# Master_Board_v1_110116.net
KiCad netlist of a schematic drawn in Altium Designer
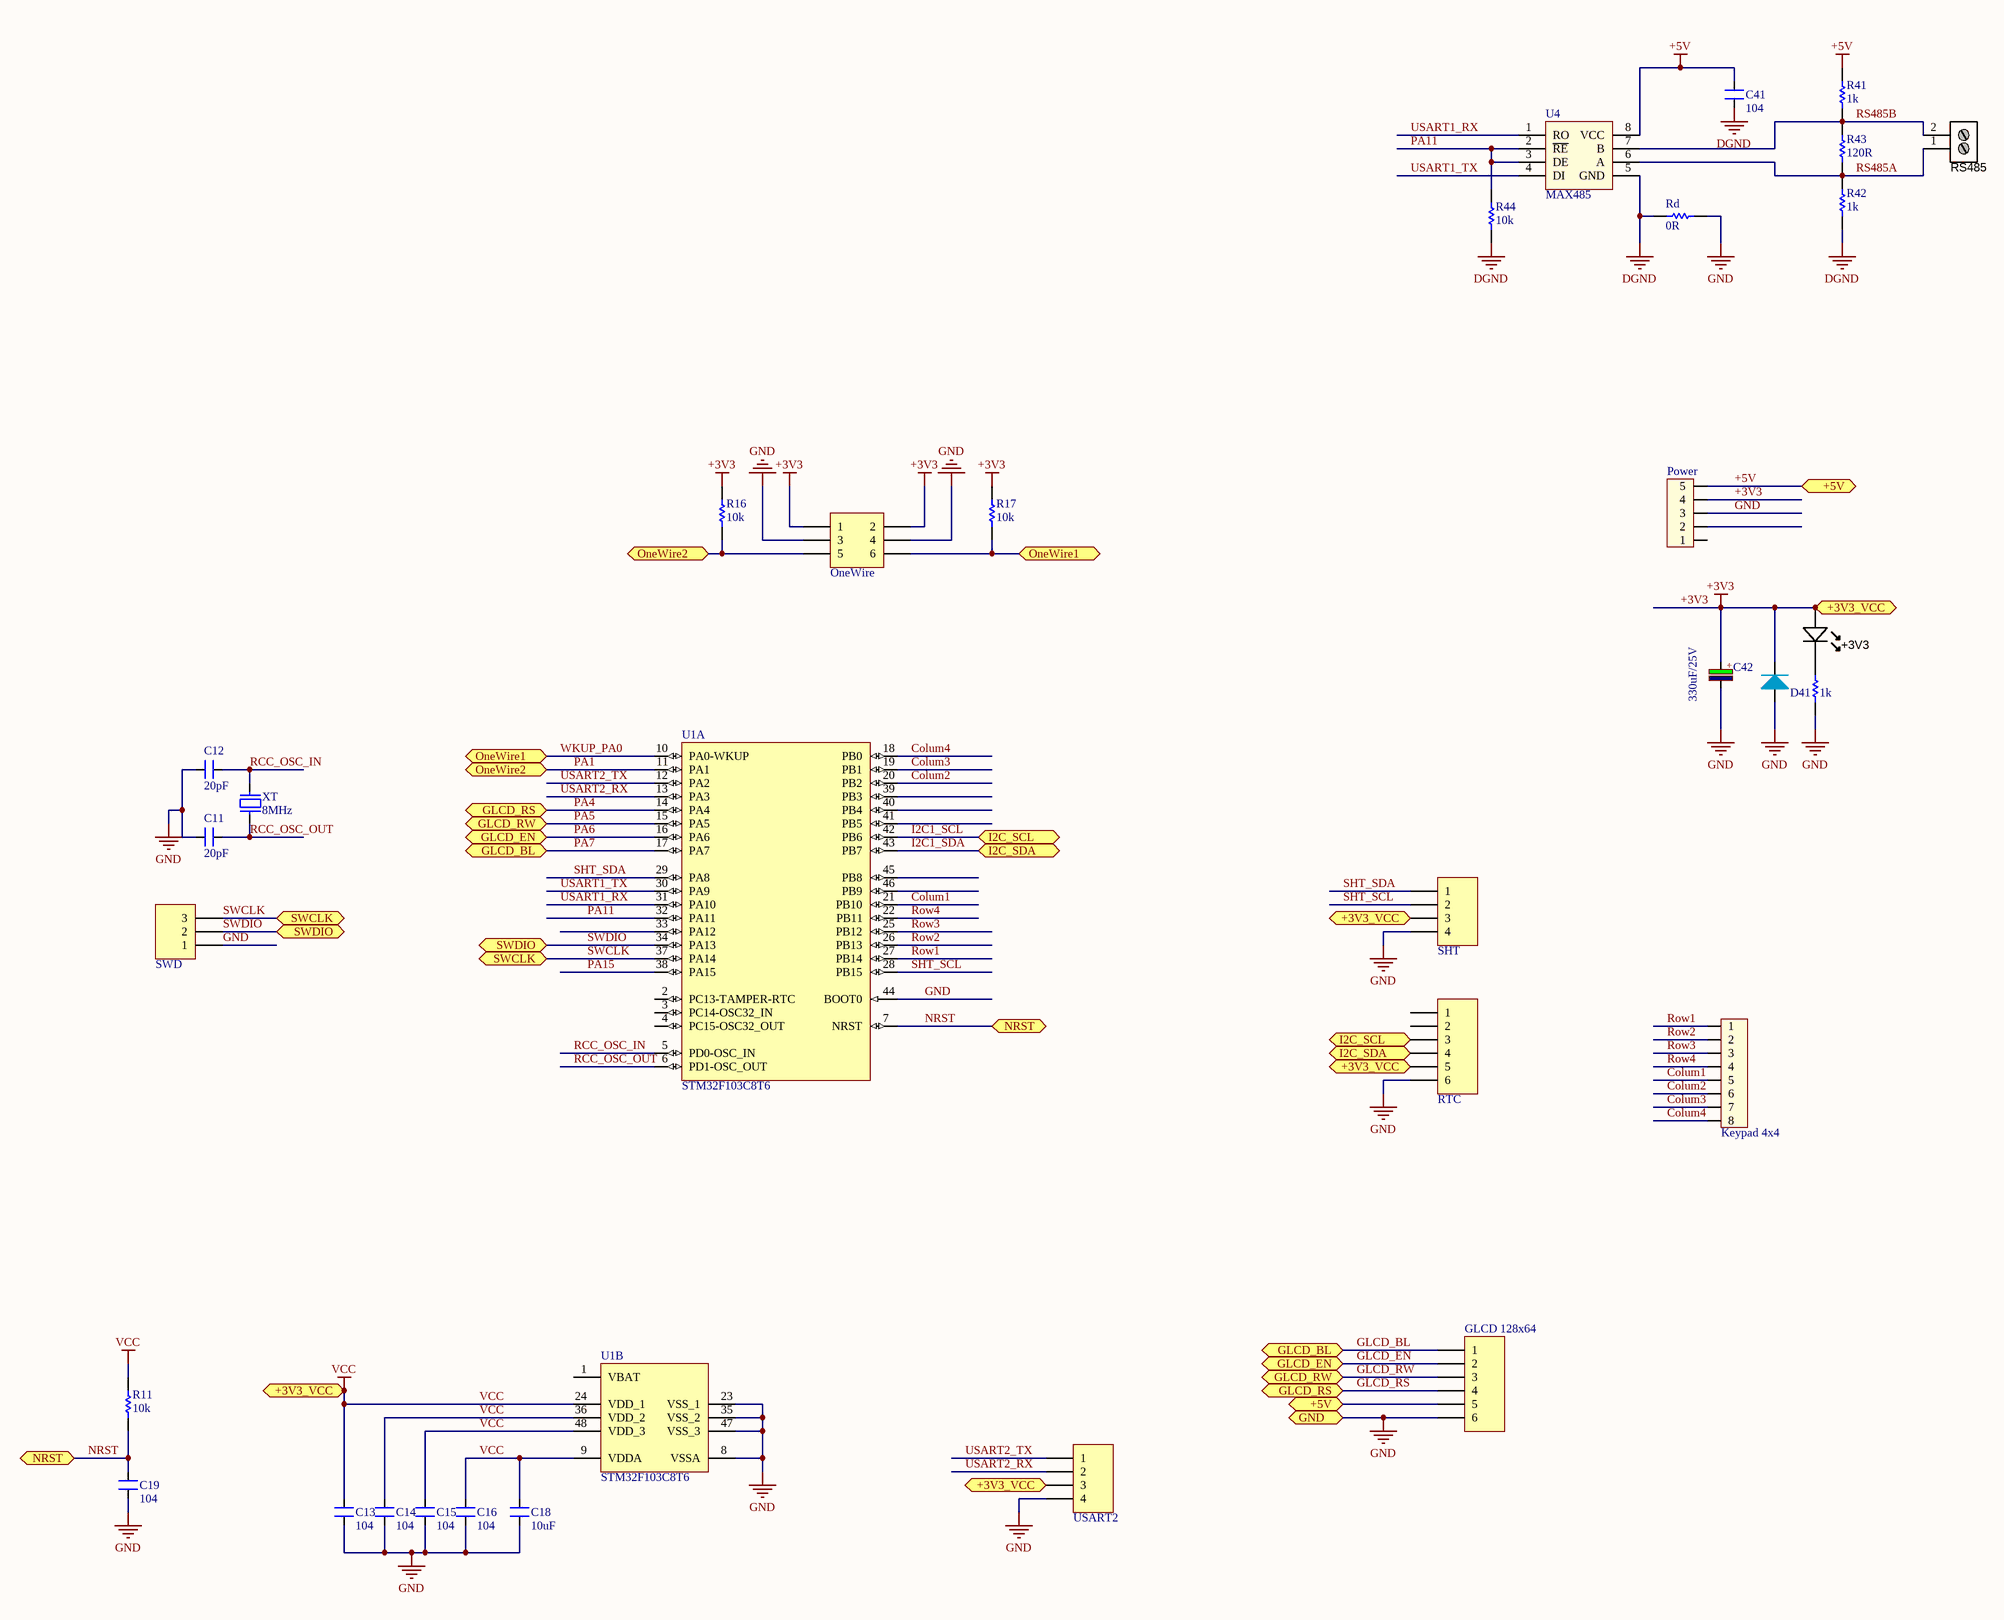
[diagram p0: Master_Board_v1_110116.SchDoc]

(export (version "E")
  (design (tool "Eeschema 10.0.6"))
  (components
    (comp (ref "+3V3")
      (value "Blue")
      (footprint "LED-0805-K")
      (description "LED 0805 SMD Blue 100mcd 470nm")
      (libsource (lib "PBL - Light Sources") (part "LED_SMD_Blue_0805_100mcd"))
    )
    (comp (ref "C11")
      (value "20pF")
      (footprint "CAPC1608N")
      (fields (field (name "Comment") "Cap_22p_0603"))
      (libsource (lib "Tuan") (part "CAP NP"))
    )
    (comp (ref "C12")
      (value "20pF")
      (footprint "CAPC1608N")
      (fields (field (name "Comment") "Cap_22p_0603"))
      (libsource (lib "Tuan") (part "CAP NP"))
    )
    (comp (ref "C13")
      (value "104")
      (footprint "CAPC1608N")
      (fields (field (name "Comment") "Cap_104_0603"))
      (libsource (lib "Tuan") (part "CAP NP"))
    )
    (comp (ref "C14")
      (value "104")
      (footprint "CAPC1608N")
      (fields (field (name "Comment") "Cap_104_0603"))
      (libsource (lib "Tuan") (part "CAP NP"))
    )
    (comp (ref "C15")
      (value "104")
      (footprint "CAPC1608N")
      (fields (field (name "Comment") "Cap_104_0603"))
      (libsource (lib "Tuan") (part "CAP NP"))
    )
    (comp (ref "C16")
      (value "104")
      (footprint "CAPC1608N")
      (fields (field (name "Comment") "Cap_104_0603"))
      (libsource (lib "Tuan") (part "CAP NP"))
    )
    (comp (ref "C18")
      (value "10uF")
      (footprint "CAPC2012N_F")
      (fields (field (name "Comment") "Cap_10uF_0805"))
      (libsource (lib "Tuan") (part "CAP NP"))
    )
    (comp (ref "C19")
      (value "104")
      (footprint "CAPC1608N")
      (fields (field (name "Comment") "Cap_104_0603"))
      (libsource (lib "Tuan") (part "CAP NP"))
    )
    (comp (ref "C41")
      (value "104")
      (footprint "CAPC2012N_F")
      (fields (field (name "Comment") "100nF/104"))
      (libsource (lib "Tuan") (part "CAP NP"))
    )
    (comp (ref "C42")
      (value "330uF/25V")
      (footprint "CAPMP3528X210N")
      (description "Cap 1000uF/16V - 220uF/50V")
      (libsource (lib "heromap") (part "CP4"))
    )
    (comp (ref "D41") (value "Diode") (footprint "DO-214AC") (libsource (lib "Tuan") (part "Diode")))
    (comp (ref "GLCD 128x64")
      (value "Header 6")
      (footprint "HDR1X6")
      (description "Header, 6-Pin")
      (fields (field (name "PUBLISHER") "Altium Limited"))
      (libsource (lib "Miscellaneous Connectors") (part "Header 6"))
    )
    (comp (ref "Keypad 4x4")
      (value "JP8")
      (footprint "CON8")
      (description "Connector 8")
      (libsource (lib "syhaunguyen") (part "Con8"))
    )
    (comp (ref "OneWire")
      (value "Header 3X2")
      (footprint "heromap:HDR2X3")
      (description "Header, 3-Pin, Dual row")
      (fields (field (name "PUBLISHER") "Altium Limited"))
      (libsource (lib "heromap") (part "Header 3X2"))
    )
    (comp (ref "Power")
      (value "JP5")
      (footprint "heromap:CON5")
      (description "Connector 5")
      (libsource (lib "heromap") (part "Con5"))
    )
    (comp (ref "R11")
      (value "10k")
      (footprint "RESC1608N_F")
      (fields (field (name "Comment") "Res_10k_0603"))
      (libsource (lib "Tuan") (part "Res"))
    )
    (comp (ref "R16")
      (value "10k")
      (footprint "RESC2012N_F")
      (fields (field (name "Comment") "Res"))
      (libsource (lib "Tuan") (part "Res"))
    )
    (comp (ref "R17")
      (value "10k")
      (footprint "RESC2012N_F")
      (fields (field (name "Comment") "Res"))
      (libsource (lib "Tuan") (part "Res"))
    )
    (comp (ref "R41")
      (value "1k")
      (footprint "RESC2012N_F")
      (description "Tro dan")
      (libsource (lib "GPS_Clock_v12") (part "Res"))
    )
    (comp (ref "R42")
      (value "1k")
      (footprint "RESC2012N_F")
      (description "Tro dan")
      (libsource (lib "GPS_Clock_v12") (part "Res"))
    )
    (comp (ref "R43")
      (value "120R")
      (footprint "RESC2012N_F")
      (description "Tro dan")
      (fields (field (name "Comment") "330R"))
      (libsource (lib "GPS_Clock_v12") (part "Res"))
    )
    (comp (ref "R44")
      (value "10k")
      (footprint "RESC2012N_F")
      (description "Tro dan")
      (fields (field (name "Comment") "330R"))
      (libsource (lib "GPS_Clock_v12") (part "Res"))
    )
    (comp (ref "Rd")
      (value "0R")
      (footprint "RESC2012N_F")
      (fields (field (name "Comment") "Res"))
      (libsource (lib "Tuan") (part "Res"))
    )
    (comp (ref "Rled")
      (value "1k")
      (footprint "RESC2012N_F")
      (fields (field (name "Comment") "Res_0805_1k"))
      (libsource (lib "Tuan") (part "Res"))
    )
    (comp (ref "RS485")
      (value "Stackable ScrewTerm")
      (footprint "2P_PCB1")
      (description "Terminal Block Screw Type THT 2-Position 3.81mm pitch")
      (libsource (lib "PBL - Connectors") (part "2P_ScrewTerm_90S_3.81MM"))
    )
    (comp (ref "RTC")
      (value "Header 6")
      (footprint "heromap:HDR1X6")
      (description "Header, 6-Pin")
      (fields (field (name "PUBLISHER") "Altium Limited"))
      (libsource (lib "heromap") (part "Header 6"))
    )
    (comp (ref "SHT")
      (value "Header 4")
      (footprint "heromap:HDR1X4")
      (description "Header, 4-Pin")
      (fields (field (name "PUBLISHER") "Altium Limited"))
      (libsource (lib "heromap") (part "Header 4"))
    )
    (comp (ref "SWD")
      (value "Header 3")
      (footprint "heromap:HDR1X3")
      (description "Header, 3-Pin")
      (fields (field (name "PUBLISHER") "Altium Limited"))
      (libsource (lib "heromap") (part "Header 3"))
    )
    (comp (ref "U1")
      (value "STM32F103C8T6")
      (footprint "LQFT48N")
      (libsource (lib "STMicroelectronics STM32 F1") (part "STM32F103C8T6"))
    )
    (comp (ref "U4")
      (value "MAX485")
      (footprint "SO-8")
      (description "RS232 - RS485 (Same sn75176)")
      (libsource (lib "heromap") (part "MAX485"))
    )
    (comp (ref "USART2")
      (value "Header 4")
      (footprint "heromap:HDR1X4")
      (description "Header, 4-Pin")
      (fields (field (name "PUBLISHER") "Altium Limited"))
      (libsource (lib "heromap") (part "Header 4"))
    )
    (comp (ref "XT") (value "8MHz") (footprint "XT2") (libsource (lib "Tuan") (part "Crystal")))
  )
  (nets
    (net (code "1") (name "+3V3") (class "Default")
      (node (ref "+3V3") (pin "A") (pinfunction "A_A") (pintype "passive"))
      (node (ref "C13") (pin "2") (pinfunction "2_2") (pintype "passive"))
      (node (ref "C14") (pin "2") (pinfunction "2_2") (pintype "passive"))
      (node (ref "C15") (pin "2") (pinfunction "2_2") (pintype "passive"))
      (node (ref "C16") (pin "2") (pinfunction "2_2") (pintype "passive"))
      (node (ref "C18") (pin "2") (pinfunction "2_2") (pintype "passive"))
      (node (ref "C42") (pin "1") (pinfunction "1_1") (pintype "passive"))
      (node (ref "D41") (pin "2") (pinfunction "K_2") (pintype "passive"))
      (node (ref "OneWire") (pin "1") (pinfunction "1_1") (pintype "passive"))
      (node (ref "OneWire") (pin "2") (pinfunction "2_2") (pintype "passive"))
      (node (ref "Power") (pin "4") (pinfunction "4_4") (pintype "passive"))
      (node (ref "R11") (pin "2") (pinfunction "2_2") (pintype "passive"))
      (node (ref "R16") (pin "2") (pinfunction "2_2") (pintype "passive"))
      (node (ref "R17") (pin "2") (pinfunction "2_2") (pintype "passive"))
      (node (ref "RTC") (pin "5") (pinfunction "5_5") (pintype "passive"))
      (node (ref "SHT") (pin "3") (pinfunction "3_3") (pintype "passive"))
      (node (ref "U1") (pin "24") (pinfunction "VDD_1_24") (pintype "power_in"))
      (node (ref "U1") (pin "36") (pinfunction "VDD_2_36") (pintype "power_in"))
      (node (ref "U1") (pin "48") (pinfunction "VDD_3_48") (pintype "power_in"))
      (node (ref "U1") (pin "9") (pinfunction "VDDA_9") (pintype "power_in"))
      (node (ref "USART2") (pin "3") (pinfunction "3_3") (pintype "passive"))
    )
    (net (code "2") (name "+5V") (class "Default")
      (node (ref "C41") (pin "2") (pinfunction "2_2") (pintype "passive"))
      (node (ref "GLCD 128x64") (pin "5") (pinfunction "5_5") (pintype "passive"))
      (node (ref "Power") (pin "5") (pinfunction "5_5") (pintype "passive"))
      (node (ref "R41") (pin "2") (pinfunction "2_2") (pintype "passive"))
      (node (ref "U4") (pin "8") (pinfunction "VCC_8") (pintype "passive"))
    )
    (net (code "3") (name "/Colum1") (class "Default")
      (node (ref "Keypad 4x4") (pin "5") (pinfunction "5_5") (pintype "passive"))
      (node (ref "U1") (pin "21") (pinfunction "PB10_21") (pintype "bidirectional"))
    )
    (net (code "4") (name "/Colum2") (class "Default")
      (node (ref "Keypad 4x4") (pin "6") (pinfunction "6_6") (pintype "passive"))
      (node (ref "U1") (pin "20") (pinfunction "PB2_20") (pintype "bidirectional"))
    )
    (net (code "5") (name "/Colum3") (class "Default")
      (node (ref "Keypad 4x4") (pin "7") (pinfunction "7_7") (pintype "passive"))
      (node (ref "U1") (pin "19") (pinfunction "PB1_19") (pintype "bidirectional"))
    )
    (net (code "6") (name "/Colum4") (class "Default")
      (node (ref "Keypad 4x4") (pin "8") (pinfunction "8_8") (pintype "passive"))
      (node (ref "U1") (pin "18") (pinfunction "PB0_18") (pintype "bidirectional"))
    )
    (net (code "7") (name "/GLCD_BL") (class "Default")
      (node (ref "GLCD 128x64") (pin "1") (pinfunction "1_1") (pintype "passive"))
      (node (ref "U1") (pin "17") (pinfunction "PA7_17") (pintype "bidirectional"))
    )
    (net (code "8") (name "/GLCD_EN") (class "Default")
      (node (ref "GLCD 128x64") (pin "2") (pinfunction "2_2") (pintype "passive"))
      (node (ref "U1") (pin "16") (pinfunction "PA6_16") (pintype "bidirectional"))
    )
    (net (code "9") (name "/GLCD_RS") (class "Default")
      (node (ref "GLCD 128x64") (pin "4") (pinfunction "4_4") (pintype "passive"))
      (node (ref "U1") (pin "14") (pinfunction "PA4_14") (pintype "bidirectional"))
    )
    (net (code "10") (name "/GLCD_RW") (class "Default")
      (node (ref "GLCD 128x64") (pin "3") (pinfunction "3_3") (pintype "passive"))
      (node (ref "U1") (pin "15") (pinfunction "PA5_15") (pintype "bidirectional"))
    )
    (net (code "11") (name "/I2C1_SCL") (class "Default")
      (node (ref "RTC") (pin "3") (pinfunction "3_3") (pintype "passive"))
      (node (ref "U1") (pin "42") (pinfunction "PB6_42") (pintype "bidirectional"))
    )
    (net (code "12") (name "/I2C1_SDA") (class "Default")
      (node (ref "RTC") (pin "4") (pinfunction "4_4") (pintype "passive"))
      (node (ref "U1") (pin "43") (pinfunction "PB7_43") (pintype "bidirectional"))
    )
    (net (code "13") (name "/NRST") (class "Default")
      (node (ref "C19") (pin "2") (pinfunction "2_2") (pintype "passive"))
      (node (ref "R11") (pin "1") (pinfunction "1_1") (pintype "passive"))
      (node (ref "U1") (pin "7") (pinfunction "NRST_7") (pintype "bidirectional"))
    )
    (net (code "14") (name "/PA1") (class "Default")
      (node (ref "OneWire") (pin "5") (pinfunction "5_5") (pintype "passive"))
      (node (ref "R16") (pin "1") (pinfunction "1_1") (pintype "passive"))
      (node (ref "U1") (pin "11") (pinfunction "PA1_11") (pintype "bidirectional"))
    )
    (net (code "15") (name "/PA11") (class "Default")
      (node (ref "R44") (pin "2") (pinfunction "2_2") (pintype "passive"))
      (node (ref "U1") (pin "32") (pinfunction "PA11_32") (pintype "bidirectional"))
      (node (ref "U4") (pin "2") (pinfunction "~{RE}_2") (pintype "passive"))
      (node (ref "U4") (pin "3") (pinfunction "DE_3") (pintype "passive"))
    )
    (net (code "16") (name "/PA15") (class "Default")
      (node (ref "U1") (pin "38") (pinfunction "PA15_38") (pintype "bidirectional"))
    )
    (net (code "17") (name "/RCC_OSC_IN") (class "Default")
      (node (ref "C12") (pin "1") (pinfunction "1_1") (pintype "passive"))
      (node (ref "U1") (pin "5") (pinfunction "PD0-OSC_IN_5") (pintype "bidirectional"))
      (node (ref "XT") (pin "2") (pinfunction "2_2") (pintype "passive"))
    )
    (net (code "18") (name "/RCC_OSC_OUT") (class "Default")
      (node (ref "C11") (pin "1") (pinfunction "1_1") (pintype "passive"))
      (node (ref "U1") (pin "6") (pinfunction "PD1-OSC_OUT_6") (pintype "bidirectional"))
      (node (ref "XT") (pin "1") (pinfunction "1_1") (pintype "passive"))
    )
    (net (code "19") (name "/RS485A") (class "Default")
      (node (ref "R42") (pin "2") (pinfunction "2_2") (pintype "passive"))
      (node (ref "R43") (pin "1") (pinfunction "1_1") (pintype "passive"))
      (node (ref "RS485") (pin "1") (pinfunction "1_1") (pintype "passive"))
      (node (ref "U4") (pin "6") (pinfunction "A_6") (pintype "passive"))
    )
    (net (code "20") (name "/RS485B") (class "Default")
      (node (ref "R41") (pin "1") (pinfunction "1_1") (pintype "passive"))
      (node (ref "R43") (pin "2") (pinfunction "2_2") (pintype "passive"))
      (node (ref "RS485") (pin "2") (pinfunction "2_2") (pintype "passive"))
      (node (ref "U4") (pin "7") (pinfunction "B_7") (pintype "passive"))
    )
    (net (code "21") (name "/Row1") (class "Default")
      (node (ref "Keypad 4x4") (pin "1") (pinfunction "1_1") (pintype "passive"))
      (node (ref "U1") (pin "27") (pinfunction "PB14_27") (pintype "bidirectional"))
    )
    (net (code "22") (name "/Row2") (class "Default")
      (node (ref "Keypad 4x4") (pin "2") (pinfunction "2_2") (pintype "passive"))
      (node (ref "U1") (pin "26") (pinfunction "PB13_26") (pintype "bidirectional"))
    )
    (net (code "23") (name "/Row3") (class "Default")
      (node (ref "Keypad 4x4") (pin "3") (pinfunction "3_3") (pintype "passive"))
      (node (ref "U1") (pin "25") (pinfunction "PB12_25") (pintype "bidirectional"))
    )
    (net (code "24") (name "/Row4") (class "Default")
      (node (ref "Keypad 4x4") (pin "4") (pinfunction "4_4") (pintype "passive"))
      (node (ref "U1") (pin "22") (pinfunction "PB11_22") (pintype "bidirectional"))
    )
    (net (code "25") (name "/SHT_SCL") (class "Default")
      (node (ref "SHT") (pin "2") (pinfunction "2_2") (pintype "passive"))
      (node (ref "U1") (pin "28") (pinfunction "PB15_28") (pintype "bidirectional"))
    )
    (net (code "26") (name "/SHT_SDA") (class "Default")
      (node (ref "SHT") (pin "1") (pinfunction "1_1") (pintype "passive"))
      (node (ref "U1") (pin "29") (pinfunction "PA8_29") (pintype "bidirectional"))
    )
    (net (code "27") (name "/SWCLK") (class "Default")
      (node (ref "SWD") (pin "3") (pinfunction "3_3") (pintype "passive"))
      (node (ref "U1") (pin "37") (pinfunction "PA14_37") (pintype "bidirectional"))
    )
    (net (code "28") (name "/SWDIO") (class "Default")
      (node (ref "SWD") (pin "2") (pinfunction "2_2") (pintype "passive"))
      (node (ref "U1") (pin "34") (pinfunction "PA13_34") (pintype "bidirectional"))
    )
    (net (code "29") (name "/USART1_RX") (class "Default")
      (node (ref "U1") (pin "31") (pinfunction "PA10_31") (pintype "bidirectional"))
      (node (ref "U4") (pin "1") (pinfunction "RO_1") (pintype "passive"))
    )
    (net (code "30") (name "/USART1_TX") (class "Default")
      (node (ref "U1") (pin "30") (pinfunction "PA9_30") (pintype "bidirectional"))
      (node (ref "U4") (pin "4") (pinfunction "DI_4") (pintype "passive"))
    )
    (net (code "31") (name "/USART2_RX") (class "Default")
      (node (ref "U1") (pin "13") (pinfunction "PA3_13") (pintype "bidirectional"))
      (node (ref "USART2") (pin "2") (pinfunction "2_2") (pintype "passive"))
    )
    (net (code "32") (name "/USART2_TX") (class "Default")
      (node (ref "U1") (pin "12") (pinfunction "PA2_12") (pintype "bidirectional"))
      (node (ref "USART2") (pin "1") (pinfunction "1_1") (pintype "passive"))
    )
    (net (code "33") (name "/WKUP_PA0") (class "Default")
      (node (ref "OneWire") (pin "6") (pinfunction "6_6") (pintype "passive"))
      (node (ref "R17") (pin "1") (pinfunction "1_1") (pintype "passive"))
      (node (ref "U1") (pin "10") (pinfunction "PA0-WKUP_10") (pintype "bidirectional"))
    )
    (net (code "34") (name "DGND") (class "Default")
      (node (ref "C41") (pin "1") (pinfunction "1_1") (pintype "passive"))
      (node (ref "R42") (pin "1") (pinfunction "1_1") (pintype "passive"))
      (node (ref "R44") (pin "1") (pinfunction "1_1") (pintype "passive"))
      (node (ref "Rd") (pin "1") (pinfunction "1_1") (pintype "passive"))
      (node (ref "U4") (pin "5") (pinfunction "GND_5") (pintype "passive"))
    )
    (net (code "35") (name "GND") (class "Default")
      (node (ref "C11") (pin "2") (pinfunction "2_2") (pintype "passive"))
      (node (ref "C12") (pin "2") (pinfunction "2_2") (pintype "passive"))
      (node (ref "C13") (pin "1") (pinfunction "1_1") (pintype "passive"))
      (node (ref "C14") (pin "1") (pinfunction "1_1") (pintype "passive"))
      (node (ref "C15") (pin "1") (pinfunction "1_1") (pintype "passive"))
      (node (ref "C16") (pin "1") (pinfunction "1_1") (pintype "passive"))
      (node (ref "C18") (pin "1") (pinfunction "1_1") (pintype "passive"))
      (node (ref "C19") (pin "1") (pinfunction "1_1") (pintype "passive"))
      (node (ref "C42") (pin "2") (pinfunction "2_2") (pintype "passive"))
      (node (ref "D41") (pin "1") (pinfunction "A_1") (pintype "passive"))
      (node (ref "GLCD 128x64") (pin "6") (pinfunction "6_6") (pintype "passive"))
      (node (ref "OneWire") (pin "3") (pinfunction "3_3") (pintype "passive"))
      (node (ref "OneWire") (pin "4") (pinfunction "4_4") (pintype "passive"))
      (node (ref "Power") (pin "3") (pinfunction "3_3") (pintype "passive"))
      (node (ref "RTC") (pin "6") (pinfunction "6_6") (pintype "passive"))
      (node (ref "Rd") (pin "2") (pinfunction "2_2") (pintype "passive"))
      (node (ref "Rled") (pin "2") (pinfunction "2_2") (pintype "passive"))
      (node (ref "SHT") (pin "4") (pinfunction "4_4") (pintype "passive"))
      (node (ref "SWD") (pin "1") (pinfunction "1_1") (pintype "passive"))
      (node (ref "U1") (pin "23") (pinfunction "VSS_1_23") (pintype "power_in"))
      (node (ref "U1") (pin "35") (pinfunction "VSS_2_35") (pintype "power_in"))
      (node (ref "U1") (pin "44") (pinfunction "BOOT0_44") (pintype "input"))
      (node (ref "U1") (pin "47") (pinfunction "VSS_3_47") (pintype "power_in"))
      (node (ref "U1") (pin "8") (pinfunction "VSSA_8") (pintype "power_in"))
      (node (ref "USART2") (pin "4") (pinfunction "4_4") (pintype "passive"))
    )
    (net (code "36") (name "Net-(+3V3-PadK)") (class "Default")
      (node (ref "+3V3") (pin "K") (pinfunction "K_K") (pintype "passive"))
      (node (ref "Rled") (pin "1") (pinfunction "1_1") (pintype "passive"))
    )
    (net (code "37") (name "unconnected-(Power-Pad1)") (class "Default")
      (node (ref "Power") (pin "1") (pinfunction "1_1") (pintype "passive"))
    )
    (net (code "38") (name "unconnected-(Power-Pad2)") (class "Default")
      (node (ref "Power") (pin "2") (pinfunction "2_2") (pintype "passive"))
    )
    (net (code "39") (name "unconnected-(RTC-Pad1)") (class "Default")
      (node (ref "RTC") (pin "1") (pinfunction "1_1") (pintype "passive"))
    )
    (net (code "40") (name "unconnected-(RTC-Pad2)") (class "Default")
      (node (ref "RTC") (pin "2") (pinfunction "2_2") (pintype "passive"))
    )
    (net (code "41") (name "unconnected-(U1A-PA12-Pad33)") (class "Default")
      (node (ref "U1") (pin "33") (pinfunction "PA12_33") (pintype "bidirectional"))
    )
    (net (code "42") (name "unconnected-(U1A-PB3-Pad39)") (class "Default")
      (node (ref "U1") (pin "39") (pinfunction "PB3_39") (pintype "bidirectional"))
    )
    (net (code "43") (name "unconnected-(U1A-PB4-Pad40)") (class "Default")
      (node (ref "U1") (pin "40") (pinfunction "PB4_40") (pintype "bidirectional"))
    )
    (net (code "44") (name "unconnected-(U1A-PB5-Pad41)") (class "Default")
      (node (ref "U1") (pin "41") (pinfunction "PB5_41") (pintype "bidirectional"))
    )
    (net (code "45") (name "unconnected-(U1A-PB8-Pad45)") (class "Default")
      (node (ref "U1") (pin "45") (pinfunction "PB8_45") (pintype "bidirectional"))
    )
    (net (code "46") (name "unconnected-(U1A-PB9-Pad46)") (class "Default")
      (node (ref "U1") (pin "46") (pinfunction "PB9_46") (pintype "bidirectional"))
    )
    (net (code "47") (name "unconnected-(U1A-PC13-TAMPER-RTC-Pad2)") (class "Default")
      (node (ref "U1") (pin "2") (pinfunction "PC13-TAMPER-RTC_2") (pintype "bidirectional"))
    )
    (net (code "48") (name "unconnected-(U1A-PC14-OSC32_IN-Pad3)") (class "Default")
      (node (ref "U1") (pin "3") (pinfunction "PC14-OSC32_IN_3") (pintype "bidirectional"))
    )
    (net (code "49") (name "unconnected-(U1A-PC15-OSC32_OUT-Pad4)") (class "Default")
      (node (ref "U1") (pin "4") (pinfunction "PC15-OSC32_OUT_4") (pintype "bidirectional"))
    )
    (net (code "50") (name "unconnected-(U1B-VBAT-Pad1)") (class "Default")
      (node (ref "U1") (pin "1") (pinfunction "VBAT_1") (pintype "power_in"))
    )
  )
)
